# HighVolBoost.net
KiCad netlist of a schematic drawn in Altium Designer
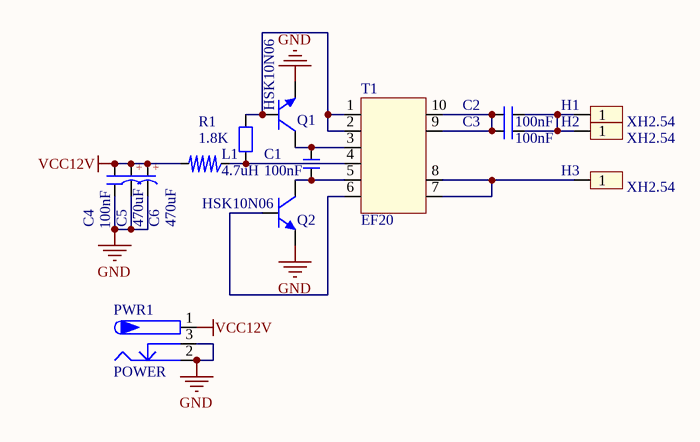
[diagram p0: HighVolBoost.SchDoc]

(export (version "E")
  (design (tool "Eeschema 10.0.6"))
  (components
    (comp (ref "C1")
      (value "100nF")
      (footprint "CY 10*14*5")
      (description "无极性贴片电容")
      (libsource (lib "LovelessingSch") (part "C"))
    )
    (comp (ref "C2")
      (value "100nF")
      (footprint "CY 7.5*8*4")
      (description "无极性贴片电容")
      (libsource (lib "LovelessingSch") (part "C"))
    )
    (comp (ref "C3")
      (value "100nF")
      (footprint "CY 7.5*8*4")
      (description "无极性贴片电容")
      (libsource (lib "LovelessingSch") (part "C"))
    )
    (comp (ref "C4")
      (value "100nF")
      (footprint "C 0805_L")
      (description "无极性贴片电容")
      (libsource (lib "LovelessingSch") (part "C"))
    )
    (comp (ref "C5")
      (value "470uF")
      (footprint "CM D(6.3*7.7)")
      (description "贴片电解电容")
      (libsource (lib "LovelessingSch") (part "C-CM"))
    )
    (comp (ref "C6")
      (value "470uF")
      (footprint "CM D(6.3*7.7)")
      (description "贴片电解电容")
      (libsource (lib "LovelessingSch") (part "C-CM"))
    )
    (comp (ref "H1")
      (value "XH2.54")
      (footprint "HDR2.54-LI-1P")
      (description "端子")
      (libsource (lib "LovelessingSch") (part "Header_1P"))
    )
    (comp (ref "H2")
      (value "XH2.54")
      (footprint "HDR2.54-LI-1P")
      (description "端子")
      (libsource (lib "LovelessingSch") (part "Header_1P"))
    )
    (comp (ref "H3")
      (value "XH2.54")
      (footprint "HDR2.54-LI-1P")
      (description "端子")
      (libsource (lib "LovelessingSch") (part "Header_1P"))
    )
    (comp (ref "L1")
      (value "4.7uH")
      (footprint "PK0810")
      (description "电感")
      (libsource (lib "LovelessingSch") (part "L_SOP"))
    )
    (comp (ref "PWR1")
      (value "POWER")
      (footprint "DC-005")
      (description "低压电源接口")
      (libsource (lib "LovelessingSch") (part "P-DC"))
    )
    (comp (ref "Q1")
      (value "HSK10N06")
      (footprint "SOT89_N")
      (description "高频放大-NPN型")
      (libsource (lib "LovelessingSch") (part "8050-SMD"))
    )
    (comp (ref "Q2")
      (value "HSK10N06")
      (footprint "SOT89_N")
      (description "高频放大-NPN型")
      (libsource (lib "LovelessingSch") (part "8050-SMD"))
    )
    (comp (ref "R1")
      (value "1.8K")
      (footprint "R 0805_L")
      (description "贴片电阻")
      (libsource (lib "LovelessingSch") (part "R"))
    )
    (comp (ref "T1")
      (value "EF20")
      (footprint "BYQ_HVB")
      (description "高压变压器")
      (libsource (lib "Schlib1") (part "BYQ_HVB"))
    )
  )
  (nets
    (net (code "1") (name "GND") (class "Default")
      (node (ref "C4") (pin "1") (pinfunction "1_1") (pintype "passive"))
      (node (ref "C5") (pin "2") (pinfunction "K_2") (pintype "passive"))
      (node (ref "C6") (pin "2") (pinfunction "K_2") (pintype "passive"))
      (node (ref "PWR1") (pin "2") (pintype "power_in"))
      (node (ref "PWR1") (pin "3") (pintype "power_in"))
      (node (ref "Q1") (pin "3") (pinfunction "E_3") (pintype "passive"))
      (node (ref "Q2") (pin "3") (pinfunction "E_3") (pintype "passive"))
    )
    (net (code "2") (name "Net-(C2-Pad1)") (class "Default")
      (node (ref "C2") (pin "1") (pinfunction "1_1") (pintype "passive"))
      (node (ref "C3") (pin "1") (pinfunction "1_1") (pintype "passive"))
      (node (ref "H1") (pin "1") (pinfunction "1_1") (pintype "passive"))
      (node (ref "H2") (pin "1") (pinfunction "1_1") (pintype "passive"))
    )
    (net (code "3") (name "Net-(C2-Pad2)") (class "Default")
      (node (ref "C2") (pin "2") (pinfunction "2_2") (pintype "passive"))
      (node (ref "C3") (pin "2") (pinfunction "2_2") (pintype "passive"))
      (node (ref "T1") (pin "10") (pintype "passive"))
      (node (ref "T1") (pin "9") (pintype "passive"))
    )
    (net (code "4") (name "Net-(H3-Pad1)") (class "Default")
      (node (ref "H3") (pin "1") (pinfunction "1_1") (pintype "passive"))
      (node (ref "T1") (pin "7") (pintype "passive"))
      (node (ref "T1") (pin "8") (pintype "passive"))
    )
    (net (code "5") (name "Net-(L1-Pad1)") (class "Default")
      (node (ref "L1") (pin "1") (pinfunction "1_1") (pintype "passive"))
      (node (ref "R1") (pin "1") (pinfunction "1_1") (pintype "passive"))
      (node (ref "T1") (pin "4") (pintype "passive"))
    )
    (net (code "6") (name "Net-(Q1-B)") (class "Default")
      (node (ref "Q1") (pin "1") (pinfunction "B_1") (pintype "passive"))
      (node (ref "R1") (pin "2") (pinfunction "2_2") (pintype "passive"))
      (node (ref "T1") (pin "1") (pintype "passive"))
      (node (ref "T1") (pin "2") (pintype "passive"))
    )
    (net (code "7") (name "Net-(Q1-C)") (class "Default")
      (node (ref "C1") (pin "2") (pinfunction "2_2") (pintype "passive"))
      (node (ref "Q1") (pin "2") (pinfunction "C_2") (pintype "passive"))
      (node (ref "T1") (pin "3") (pintype "passive"))
    )
    (net (code "8") (name "Net-(Q2-B)") (class "Default")
      (node (ref "Q2") (pin "1") (pinfunction "B_1") (pintype "passive"))
      (node (ref "T1") (pin "6") (pintype "passive"))
    )
    (net (code "9") (name "Net-(Q2-C)") (class "Default")
      (node (ref "C1") (pin "1") (pinfunction "1_1") (pintype "passive"))
      (node (ref "Q2") (pin "2") (pinfunction "C_2") (pintype "passive"))
      (node (ref "T1") (pin "5") (pintype "passive"))
    )
    (net (code "10") (name "VCC12V") (class "Default")
      (node (ref "C4") (pin "2") (pinfunction "2_2") (pintype "passive"))
      (node (ref "C5") (pin "1") (pinfunction "A_1") (pintype "passive"))
      (node (ref "C6") (pin "1") (pinfunction "A_1") (pintype "passive"))
      (node (ref "L1") (pin "2") (pinfunction "2_2") (pintype "passive"))
      (node (ref "PWR1") (pin "1") (pintype "power_in"))
    )
  )
)
